# Trans_Main_Board_ESP32_NEW_Rev1_2.net
KiCad netlist of a schematic drawn in EAGLE
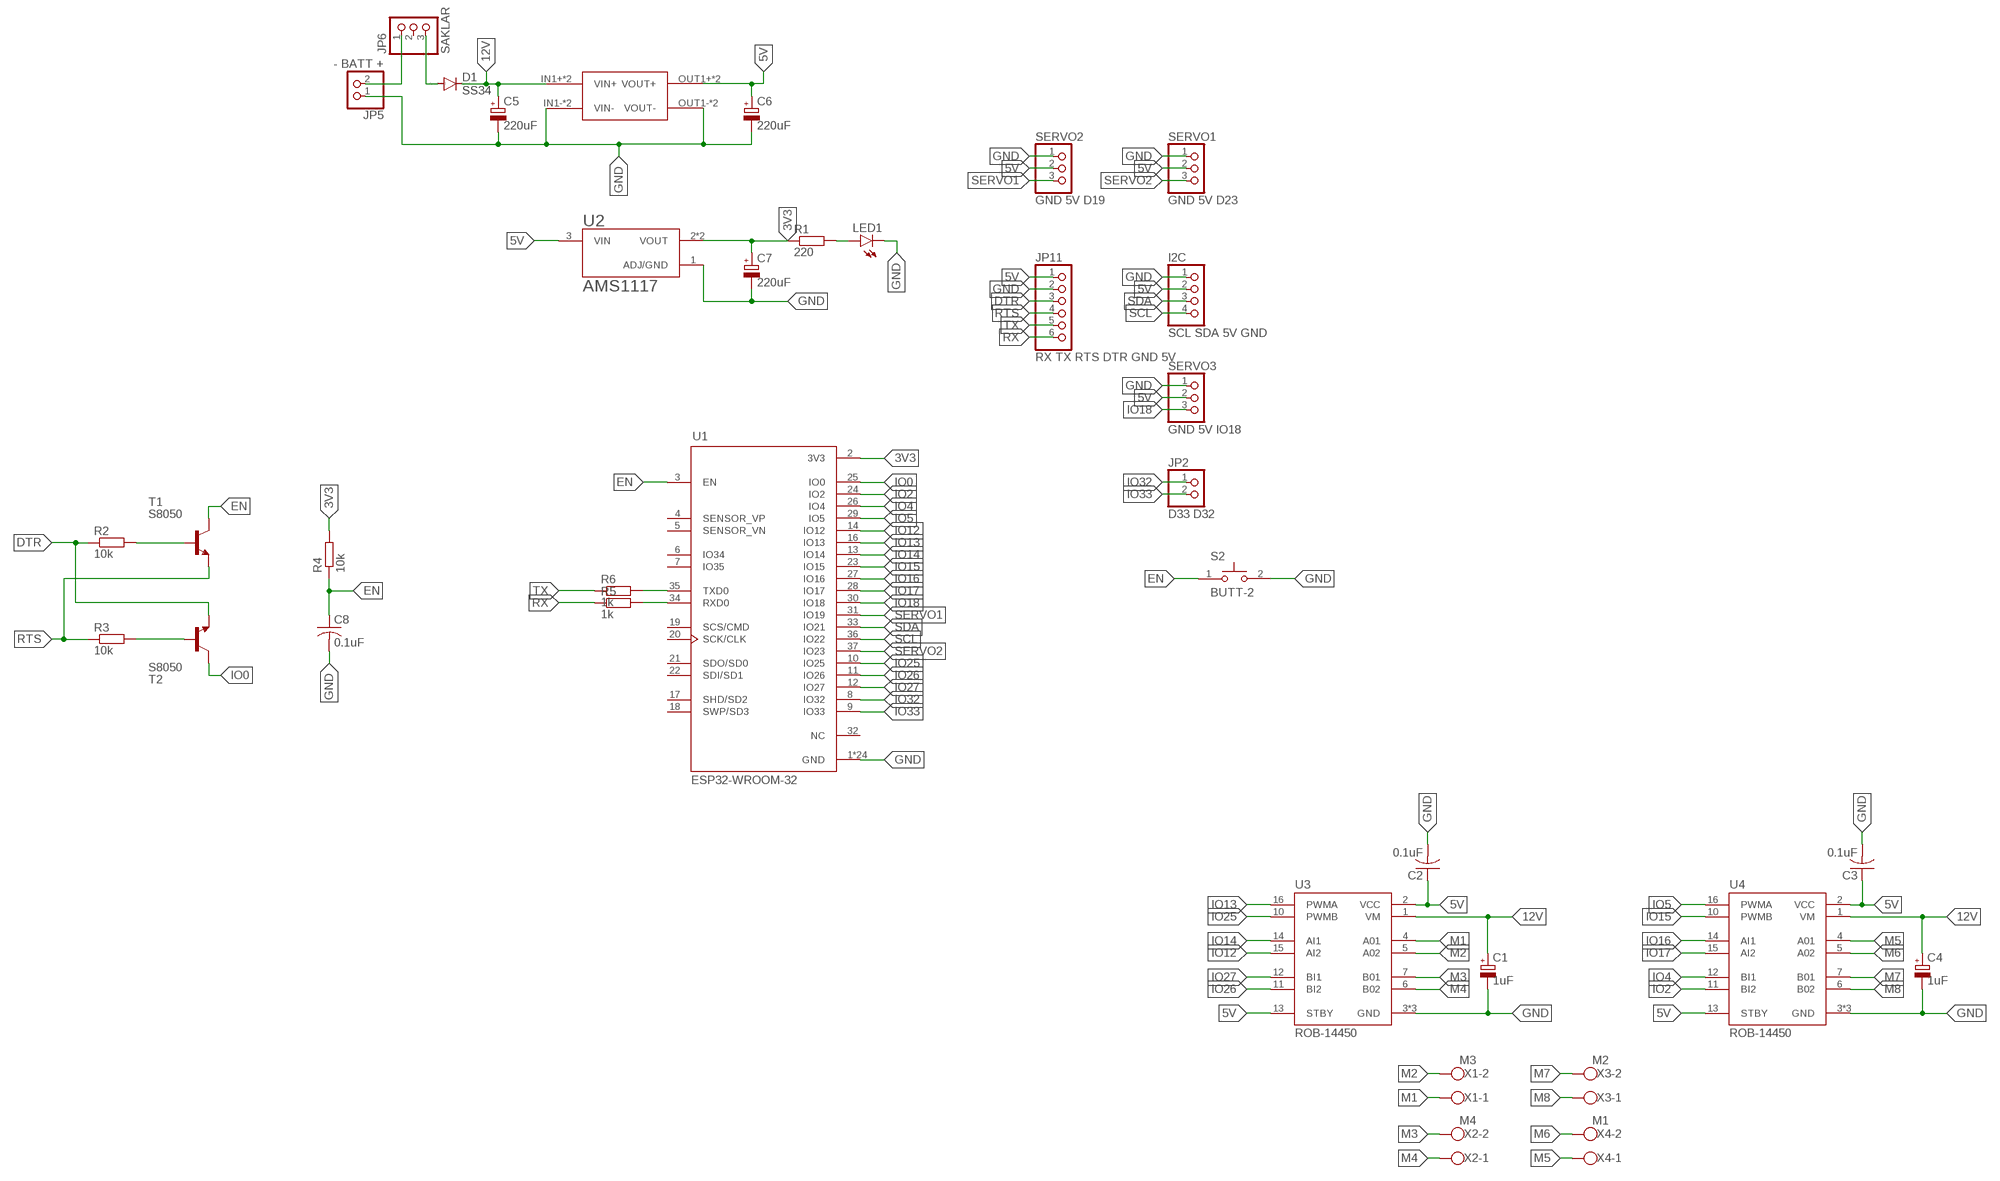
[diagram p0: schematic, sheet 1]

(export (version "E")
  (design (tool "Eeschema 10.0.6"))
  (components
    (comp (ref "C1")
      (value "1uF")
      (footprint "eagle-import:E2-5")
      (libsource (lib "eagle-import") (part "CPOL-EUE2-5"))
    )
    (comp (ref "C2")
      (value "0.1uF")
      (footprint "eagle-import:C1206")
      (libsource (lib "eagle-import") (part "C-USC1206"))
    )
    (comp (ref "C3")
      (value "0.1uF")
      (footprint "eagle-import:C1206")
      (libsource (lib "eagle-import") (part "C-USC1206"))
    )
    (comp (ref "C4")
      (value "1uF")
      (footprint "eagle-import:E2-5")
      (libsource (lib "eagle-import") (part "CPOL-EUE2-5"))
    )
    (comp (ref "C5")
      (value "220uF")
      (footprint "eagle-import:E2-5")
      (libsource (lib "eagle-import") (part "CPOL-EUE2-5"))
    )
    (comp (ref "C6")
      (value "220uF")
      (footprint "eagle-import:E2-5")
      (libsource (lib "eagle-import") (part "CPOL-EUE2-5"))
    )
    (comp (ref "C7")
      (value "220uF")
      (footprint "eagle-import:E2-5")
      (libsource (lib "eagle-import") (part "CPOL-EUE2-5"))
    )
    (comp (ref "C8")
      (value "0.1uF")
      (footprint "eagle-import:C1206")
      (libsource (lib "eagle-import") (part "C-USC1206"))
    )
    (comp (ref "D1")
      (value "SS34")
      (footprint "eagle-import:DO-214AC")
      (libsource (lib "eagle-import") (part "DIODE-DO-214AC"))
    )
    (comp (ref "I2C")
      (value "SCL SDA 5V GND")
      (footprint "eagle-import:1X04")
      (libsource (lib "eagle-import") (part "PINHD-1X4"))
    )
    (comp (ref "JP2")
      (value "D33 D32")
      (footprint "eagle-import:1X02")
      (libsource (lib "eagle-import") (part "PINHD-1X2"))
    )
    (comp (ref "JP5")
      (value "- BATT +")
      (footprint "eagle-import:1X02")
      (libsource (lib "eagle-import") (part "PINHD-1X2"))
    )
    (comp (ref "JP6")
      (value "SAKLAR")
      (footprint "eagle-import:1X03")
      (libsource (lib "eagle-import") (part "PINHD-1X3"))
    )
    (comp (ref "JP11")
      (value "RX TX RTS DTR GND 5V")
      (footprint "eagle-import:1X06")
      (libsource (lib "eagle-import") (part "PINHD-1X6"))
    )
    (comp (ref "LED1")
      (value "LEDCHIPLED_1206")
      (footprint "eagle-import:CHIPLED_1206")
      (libsource (lib "eagle-import") (part "LEDCHIPLED_1206"))
    )
    (comp (ref "R1")
      (value "220")
      (footprint "eagle-import:R1206")
      (libsource (lib "eagle-import") (part "R-EU_R1206"))
    )
    (comp (ref "R2")
      (value "10k")
      (footprint "eagle-import:R1206")
      (libsource (lib "eagle-import") (part "R-EU_R1206"))
    )
    (comp (ref "R3")
      (value "10k")
      (footprint "eagle-import:R1206")
      (libsource (lib "eagle-import") (part "R-EU_R1206"))
    )
    (comp (ref "R4")
      (value "10k")
      (footprint "eagle-import:R1206")
      (libsource (lib "eagle-import") (part "R-EU_R1206"))
    )
    (comp (ref "R5")
      (value "1k")
      (footprint "eagle-import:R1206")
      (libsource (lib "eagle-import") (part "R-EU_R1206"))
    )
    (comp (ref "R6")
      (value "1k")
      (footprint "eagle-import:R1206")
      (libsource (lib "eagle-import") (part "R-EU_R1206"))
    )
    (comp (ref "S2")
      (value "BUTT-2")
      (footprint "eagle-import:SW_BUTT-2")
      (fields (field (name "MF") "Gravitech"))
      (libsource (lib "eagle-import") (part "BUTT-2"))
    )
    (comp (ref "SERVO1")
      (value "GND 5V D23")
      (footprint "eagle-import:1X03")
      (libsource (lib "eagle-import") (part "PINHD-1X3"))
    )
    (comp (ref "SERVO2")
      (value "GND 5V D19")
      (footprint "eagle-import:1X03")
      (libsource (lib "eagle-import") (part "PINHD-1X3"))
    )
    (comp (ref "SERVO3")
      (value "GND 5V IO18")
      (footprint "eagle-import:1X03")
      (libsource (lib "eagle-import") (part "PINHD-1X3"))
    )
    (comp (ref "T1")
      (value "S8050")
      (footprint "eagle-import:SOT23")
      (libsource (lib "eagle-import") (part "BC846"))
    )
    (comp (ref "T2")
      (value "S8050")
      (footprint "eagle-import:SOT23")
      (libsource (lib "eagle-import") (part "BC846"))
    )
    (comp (ref "U$1")
      (value "MP1584")
      (footprint "eagle-import:DC-BRICK")
      (libsource (lib "eagle-import") (part "MP1584"))
    )
    (comp (ref "U1")
      (value "ESP32-WROOM-32")
      (footprint "eagle-import:MODULE_ESP32-WROOM-32")
      (fields (field (name "MF") "Espressif Systems"))
      (libsource (lib "eagle-import") (part "ESP32-WROOM-32"))
    )
    (comp (ref "U2")
      (value "AMS1117")
      (footprint "eagle-import:SOT229P700X180-4N")
      (fields (field (name "MF") "Advanced Monolithic Systems"))
      (libsource (lib "eagle-import") (part "AMS1117"))
    )
    (comp (ref "U3")
      (value "ROB-14450")
      (footprint "eagle-import:MODULE_ROB-14450")
      (fields (field (name "MF") "SparkFun Electronics"))
      (libsource (lib "eagle-import") (part "ROB-14450"))
    )
    (comp (ref "U4")
      (value "ROB-14450")
      (footprint "eagle-import:MODULE_ROB-14450")
      (fields (field (name "MF") "SparkFun Electronics"))
      (libsource (lib "eagle-import") (part "ROB-14450"))
    )
    (comp (ref "X1")
      (value "M3")
      (footprint "eagle-import:W237-102")
      (fields (field (name "MPN") "237-102"))
      (libsource (lib "eagle-import") (part "W237-102"))
    )
    (comp (ref "X2")
      (value "M4")
      (footprint "eagle-import:W237-102")
      (fields (field (name "MPN") "237-102"))
      (libsource (lib "eagle-import") (part "W237-102"))
    )
    (comp (ref "X3")
      (value "M2")
      (footprint "eagle-import:W237-102")
      (fields (field (name "MPN") "237-102"))
      (libsource (lib "eagle-import") (part "W237-102"))
    )
    (comp (ref "X4")
      (value "M1")
      (footprint "eagle-import:W237-102")
      (fields (field (name "MPN") "237-102"))
      (libsource (lib "eagle-import") (part "W237-102"))
    )
  )
  (nets
    (net (code "1") (name "3V3") (class "Default")
      (node (ref "C7") (pin "+") (pinfunction "+_+") (pintype "passive"))
      (node (ref "R1") (pin "1") (pinfunction "1_1") (pintype "passive"))
      (node (ref "R4") (pin "2") (pinfunction "2_2") (pintype "passive"))
      (node (ref "U1") (pin "2") (pinfunction "3V3_2") (pintype "power_in"))
      (node (ref "U2") (pin "2") (pinfunction "VOUT_2") (pintype "output"))
      (node (ref "U2") (pin "4") (pinfunction "VOUT_4") (pintype "output"))
    )
    (net (code "2") (name "5V") (class "Default")
      (node (ref "C2") (pin "1") (pinfunction "1_1") (pintype "passive"))
      (node (ref "C3") (pin "1") (pinfunction "1_1") (pintype "passive"))
      (node (ref "C6") (pin "+") (pinfunction "+_+") (pintype "passive"))
      (node (ref "I2C") (pin "2") (pinfunction "2_2") (pintype "passive"))
      (node (ref "JP11") (pin "1") (pinfunction "1_1") (pintype "passive"))
      (node (ref "SERVO1") (pin "2") (pinfunction "2_2") (pintype "passive"))
      (node (ref "SERVO2") (pin "2") (pinfunction "2_2") (pintype "passive"))
      (node (ref "SERVO3") (pin "2") (pinfunction "2_2") (pintype "passive"))
      (node (ref "U$1") (pin "OUT1+") (pinfunction "VOUT+_OUT1+") (pintype "output"))
      (node (ref "U$1") (pin "OUT2+") (pinfunction "VOUT+_OUT2+") (pintype "output"))
      (node (ref "U2") (pin "3") (pinfunction "VIN_3") (pintype "input"))
      (node (ref "U3") (pin "13") (pinfunction "STBY_13") (pintype "input"))
      (node (ref "U3") (pin "2") (pinfunction "VCC_2") (pintype "power_in"))
      (node (ref "U4") (pin "13") (pinfunction "STBY_13") (pintype "input"))
      (node (ref "U4") (pin "2") (pinfunction "VCC_2") (pintype "power_in"))
    )
    (net (code "3") (name "12V") (class "Default")
      (node (ref "C1") (pin "+") (pinfunction "+_+") (pintype "passive"))
      (node (ref "C4") (pin "+") (pinfunction "+_+") (pintype "passive"))
      (node (ref "C5") (pin "+") (pinfunction "+_+") (pintype "passive"))
      (node (ref "D1") (pin "C") (pinfunction "C_C") (pintype "passive"))
      (node (ref "U$1") (pin "IN1+") (pinfunction "VIN+_IN1+") (pintype "input"))
      (node (ref "U$1") (pin "IN2+") (pinfunction "VIN+_IN2+") (pintype "input"))
      (node (ref "U3") (pin "1") (pinfunction "VM_1") (pintype "power_in"))
      (node (ref "U4") (pin "1") (pinfunction "VM_1") (pintype "power_in"))
    )
    (net (code "4") (name "DTR") (class "Default")
      (node (ref "JP11") (pin "3") (pinfunction "3_3") (pintype "passive"))
      (node (ref "R2") (pin "1") (pinfunction "1_1") (pintype "passive"))
      (node (ref "T2") (pin "2") (pinfunction "E_2") (pintype "passive"))
    )
    (net (code "5") (name "EN") (class "Default")
      (node (ref "C8") (pin "1") (pinfunction "1_1") (pintype "passive"))
      (node (ref "R4") (pin "1") (pinfunction "1_1") (pintype "passive"))
      (node (ref "S2") (pin "1") (pinfunction "1_1") (pintype "passive"))
      (node (ref "T1") (pin "3") (pinfunction "C_3") (pintype "passive"))
      (node (ref "U1") (pin "3") (pinfunction "EN_3") (pintype "input"))
    )
    (net (code "6") (name "GND") (class "Default")
      (node (ref "C1") (pin "-") (pinfunction "-_-") (pintype "passive"))
      (node (ref "C2") (pin "2") (pinfunction "2_2") (pintype "passive"))
      (node (ref "C3") (pin "2") (pinfunction "2_2") (pintype "passive"))
      (node (ref "C4") (pin "-") (pinfunction "-_-") (pintype "passive"))
      (node (ref "C5") (pin "-") (pinfunction "-_-") (pintype "passive"))
      (node (ref "C6") (pin "-") (pinfunction "-_-") (pintype "passive"))
      (node (ref "C7") (pin "-") (pinfunction "-_-") (pintype "passive"))
      (node (ref "C8") (pin "2") (pinfunction "2_2") (pintype "passive"))
      (node (ref "I2C") (pin "1") (pinfunction "1_1") (pintype "passive"))
      (node (ref "JP11") (pin "2") (pinfunction "2_2") (pintype "passive"))
      (node (ref "JP5") (pin "1") (pinfunction "1_1") (pintype "passive"))
      (node (ref "LED1") (pin "C") (pinfunction "C_C") (pintype "passive"))
      (node (ref "S2") (pin "2") (pinfunction "2_2") (pintype "passive"))
      (node (ref "SERVO1") (pin "1") (pinfunction "1_1") (pintype "passive"))
      (node (ref "SERVO2") (pin "1") (pinfunction "1_1") (pintype "passive"))
      (node (ref "SERVO3") (pin "1") (pinfunction "1_1") (pintype "passive"))
      (node (ref "U$1") (pin "IN1-") (pinfunction "VIN-_IN1-") (pintype "input"))
      (node (ref "U$1") (pin "IN2-") (pinfunction "VIN-_IN2-") (pintype "input"))
      (node (ref "U$1") (pin "OUT1-") (pinfunction "VOUT-_OUT1-") (pintype "output"))
      (node (ref "U$1") (pin "OUT2-") (pinfunction "VOUT-_OUT2-") (pintype "output"))
      (node (ref "U1") (pin "1") (pinfunction "GND_1") (pintype "power_in"))
      (node (ref "U1") (pin "15") (pinfunction "GND_15") (pintype "power_in"))
      (node (ref "U1") (pin "38") (pinfunction "GND_38") (pintype "power_in"))
      (node (ref "U1") (pin "39_1") (pinfunction "GND_39_1") (pintype "power_in"))
      (node (ref "U1") (pin "39_10") (pinfunction "GND_39_10") (pintype "power_in"))
      (node (ref "U1") (pin "39_11") (pinfunction "GND_39_11") (pintype "power_in"))
      (node (ref "U1") (pin "39_12") (pinfunction "GND_39_12") (pintype "power_in"))
      (node (ref "U1") (pin "39_13") (pinfunction "GND_39_13") (pintype "power_in"))
      (node (ref "U1") (pin "39_14") (pinfunction "GND_39_14") (pintype "power_in"))
      (node (ref "U1") (pin "39_15") (pinfunction "GND_39_15") (pintype "power_in"))
      (node (ref "U1") (pin "39_16") (pinfunction "GND_39_16") (pintype "power_in"))
      (node (ref "U1") (pin "39_17") (pinfunction "GND_39_17") (pintype "power_in"))
      (node (ref "U1") (pin "39_18") (pinfunction "GND_39_18") (pintype "power_in"))
      (node (ref "U1") (pin "39_19") (pinfunction "GND_39_19") (pintype "power_in"))
      (node (ref "U1") (pin "39_2") (pinfunction "GND_39_2") (pintype "power_in"))
      (node (ref "U1") (pin "39_20") (pinfunction "GND_39_20") (pintype "power_in"))
      (node (ref "U1") (pin "39_21") (pinfunction "GND_39_21") (pintype "power_in"))
      (node (ref "U1") (pin "39_3") (pinfunction "GND_39_3") (pintype "power_in"))
      (node (ref "U1") (pin "39_4") (pinfunction "GND_39_4") (pintype "power_in"))
      (node (ref "U1") (pin "39_5") (pinfunction "GND_39_5") (pintype "power_in"))
      (node (ref "U1") (pin "39_6") (pinfunction "GND_39_6") (pintype "power_in"))
      (node (ref "U1") (pin "39_7") (pinfunction "GND_39_7") (pintype "power_in"))
      (node (ref "U1") (pin "39_8") (pinfunction "GND_39_8") (pintype "power_in"))
      (node (ref "U1") (pin "39_9") (pinfunction "GND_39_9") (pintype "power_in"))
      (node (ref "U2") (pin "1") (pinfunction "ADJ/GND_1") (pintype "power_in"))
      (node (ref "U3") (pin "3") (pinfunction "GND_3") (pintype "power_in"))
      (node (ref "U3") (pin "8") (pinfunction "GND_8") (pintype "power_in"))
      (node (ref "U3") (pin "9") (pinfunction "GND_9") (pintype "power_in"))
      (node (ref "U4") (pin "3") (pinfunction "GND_3") (pintype "power_in"))
      (node (ref "U4") (pin "8") (pinfunction "GND_8") (pintype "power_in"))
      (node (ref "U4") (pin "9") (pinfunction "GND_9") (pintype "power_in"))
    )
    (net (code "7") (name "IO0") (class "Default")
      (node (ref "T2") (pin "3") (pinfunction "C_3") (pintype "passive"))
      (node (ref "U1") (pin "25") (pinfunction "IO0_25") (pintype "bidirectional"))
    )
    (net (code "8") (name "IO2") (class "Default")
      (node (ref "U1") (pin "24") (pinfunction "IO2_24") (pintype "bidirectional"))
      (node (ref "U4") (pin "11") (pinfunction "BI2_11") (pintype "input"))
    )
    (net (code "9") (name "IO4") (class "Default")
      (node (ref "U1") (pin "26") (pinfunction "IO4_26") (pintype "bidirectional"))
      (node (ref "U4") (pin "12") (pinfunction "BI1_12") (pintype "input"))
    )
    (net (code "10") (name "IO5") (class "Default")
      (node (ref "U1") (pin "29") (pinfunction "IO5_29") (pintype "bidirectional"))
      (node (ref "U4") (pin "16") (pinfunction "PWMA_16") (pintype "input"))
    )
    (net (code "11") (name "IO12") (class "Default")
      (node (ref "U1") (pin "14") (pinfunction "IO12_14") (pintype "bidirectional"))
      (node (ref "U3") (pin "15") (pinfunction "AI2_15") (pintype "input"))
    )
    (net (code "12") (name "IO13") (class "Default")
      (node (ref "U1") (pin "16") (pinfunction "IO13_16") (pintype "bidirectional"))
      (node (ref "U3") (pin "16") (pinfunction "PWMA_16") (pintype "input"))
    )
    (net (code "13") (name "IO14") (class "Default")
      (node (ref "U1") (pin "13") (pinfunction "IO14_13") (pintype "bidirectional"))
      (node (ref "U3") (pin "14") (pinfunction "AI1_14") (pintype "input"))
    )
    (net (code "14") (name "IO15") (class "Default")
      (node (ref "U1") (pin "23") (pinfunction "IO15_23") (pintype "bidirectional"))
      (node (ref "U4") (pin "10") (pinfunction "PWMB_10") (pintype "input"))
    )
    (net (code "15") (name "IO16") (class "Default")
      (node (ref "U1") (pin "27") (pinfunction "IO16_27") (pintype "bidirectional"))
      (node (ref "U4") (pin "14") (pinfunction "AI1_14") (pintype "input"))
    )
    (net (code "16") (name "IO17") (class "Default")
      (node (ref "U1") (pin "28") (pinfunction "IO17_28") (pintype "bidirectional"))
      (node (ref "U4") (pin "15") (pinfunction "AI2_15") (pintype "input"))
    )
    (net (code "17") (name "IO18") (class "Default")
      (node (ref "SERVO3") (pin "3") (pinfunction "3_3") (pintype "passive"))
      (node (ref "U1") (pin "30") (pinfunction "IO18_30") (pintype "bidirectional"))
    )
    (net (code "18") (name "IO25") (class "Default")
      (node (ref "U1") (pin "10") (pinfunction "IO25_10") (pintype "bidirectional"))
      (node (ref "U3") (pin "10") (pinfunction "PWMB_10") (pintype "input"))
    )
    (net (code "19") (name "IO26") (class "Default")
      (node (ref "U1") (pin "11") (pinfunction "IO26_11") (pintype "bidirectional"))
      (node (ref "U3") (pin "11") (pinfunction "BI2_11") (pintype "input"))
    )
    (net (code "20") (name "IO27") (class "Default")
      (node (ref "U1") (pin "12") (pinfunction "IO27_12") (pintype "bidirectional"))
      (node (ref "U3") (pin "12") (pinfunction "BI1_12") (pintype "input"))
    )
    (net (code "21") (name "IO32") (class "Default")
      (node (ref "JP2") (pin "1") (pinfunction "1_1") (pintype "passive"))
      (node (ref "U1") (pin "8") (pinfunction "IO32_8") (pintype "bidirectional"))
    )
    (net (code "22") (name "IO33") (class "Default")
      (node (ref "JP2") (pin "2") (pinfunction "2_2") (pintype "passive"))
      (node (ref "U1") (pin "9") (pinfunction "IO33_9") (pintype "bidirectional"))
    )
    (net (code "23") (name "M1") (class "Default")
      (node (ref "U3") (pin "4") (pinfunction "A01_4") (pintype "output"))
      (node (ref "X1") (pin "1") (pinfunction "KL_1") (pintype "passive"))
    )
    (net (code "24") (name "M2") (class "Default")
      (node (ref "U3") (pin "5") (pinfunction "A02_5") (pintype "output"))
      (node (ref "X1") (pin "2") (pinfunction "KL_2") (pintype "passive"))
    )
    (net (code "25") (name "M3") (class "Default")
      (node (ref "U3") (pin "7") (pinfunction "B01_7") (pintype "output"))
      (node (ref "X2") (pin "2") (pinfunction "KL_2") (pintype "passive"))
    )
    (net (code "26") (name "M4") (class "Default")
      (node (ref "U3") (pin "6") (pinfunction "B02_6") (pintype "output"))
      (node (ref "X2") (pin "1") (pinfunction "KL_1") (pintype "passive"))
    )
    (net (code "27") (name "M5") (class "Default")
      (node (ref "U4") (pin "4") (pinfunction "A01_4") (pintype "output"))
      (node (ref "X4") (pin "1") (pinfunction "KL_1") (pintype "passive"))
    )
    (net (code "28") (name "M6") (class "Default")
      (node (ref "U4") (pin "5") (pinfunction "A02_5") (pintype "output"))
      (node (ref "X4") (pin "2") (pinfunction "KL_2") (pintype "passive"))
    )
    (net (code "29") (name "M7") (class "Default")
      (node (ref "U4") (pin "7") (pinfunction "B01_7") (pintype "output"))
      (node (ref "X3") (pin "2") (pinfunction "KL_2") (pintype "passive"))
    )
    (net (code "30") (name "M8") (class "Default")
      (node (ref "U4") (pin "6") (pinfunction "B02_6") (pintype "output"))
      (node (ref "X3") (pin "1") (pinfunction "KL_1") (pintype "passive"))
    )
    (net (code "31") (name "Net-(D1-PadA)") (class "Default")
      (node (ref "D1") (pin "A") (pinfunction "A_A") (pintype "passive"))
      (node (ref "JP6") (pin "3") (pinfunction "3_3") (pintype "passive"))
    )
    (net (code "32") (name "Net-(JP5-Pad2)") (class "Default")
      (node (ref "JP5") (pin "2") (pinfunction "2_2") (pintype "passive"))
      (node (ref "JP6") (pin "1") (pinfunction "1_1") (pintype "passive"))
    )
    (net (code "33") (name "Net-(LED1-PadA)") (class "Default")
      (node (ref "LED1") (pin "A") (pinfunction "A_A") (pintype "passive"))
      (node (ref "R1") (pin "2") (pinfunction "2_2") (pintype "passive"))
    )
    (net (code "34") (name "Net-(T1-B)") (class "Default")
      (node (ref "R2") (pin "2") (pinfunction "2_2") (pintype "passive"))
      (node (ref "T1") (pin "1") (pinfunction "B_1") (pintype "passive"))
    )
    (net (code "35") (name "Net-(T2-B)") (class "Default")
      (node (ref "R3") (pin "2") (pinfunction "2_2") (pintype "passive"))
      (node (ref "T2") (pin "1") (pinfunction "B_1") (pintype "passive"))
    )
    (net (code "36") (name "Net-(U1-RXD0)") (class "Default")
      (node (ref "R5") (pin "2") (pinfunction "2_2") (pintype "passive"))
      (node (ref "U1") (pin "34") (pinfunction "RXD0_34") (pintype "bidirectional"))
    )
    (net (code "37") (name "Net-(U1-TXD0)") (class "Default")
      (node (ref "R6") (pin "2") (pinfunction "2_2") (pintype "passive"))
      (node (ref "U1") (pin "35") (pinfunction "TXD0_35") (pintype "bidirectional"))
    )
    (net (code "38") (name "RTS") (class "Default")
      (node (ref "JP11") (pin "4") (pinfunction "4_4") (pintype "passive"))
      (node (ref "R3") (pin "1") (pinfunction "1_1") (pintype "passive"))
      (node (ref "T1") (pin "2") (pinfunction "E_2") (pintype "passive"))
    )
    (net (code "39") (name "RX") (class "Default")
      (node (ref "JP11") (pin "6") (pinfunction "6_6") (pintype "passive"))
      (node (ref "R5") (pin "1") (pinfunction "1_1") (pintype "passive"))
    )
    (net (code "40") (name "SCL") (class "Default")
      (node (ref "I2C") (pin "4") (pinfunction "4_4") (pintype "passive"))
      (node (ref "U1") (pin "36") (pinfunction "IO22_36") (pintype "bidirectional"))
    )
    (net (code "41") (name "SDA") (class "Default")
      (node (ref "I2C") (pin "3") (pinfunction "3_3") (pintype "passive"))
      (node (ref "U1") (pin "33") (pinfunction "IO21_33") (pintype "bidirectional"))
    )
    (net (code "42") (name "SERVO1") (class "Default")
      (node (ref "SERVO2") (pin "3") (pinfunction "3_3") (pintype "passive"))
      (node (ref "U1") (pin "31") (pinfunction "IO19_31") (pintype "bidirectional"))
    )
    (net (code "43") (name "SERVO2") (class "Default")
      (node (ref "SERVO1") (pin "3") (pinfunction "3_3") (pintype "passive"))
      (node (ref "U1") (pin "37") (pinfunction "IO23_37") (pintype "bidirectional"))
    )
    (net (code "44") (name "TX") (class "Default")
      (node (ref "JP11") (pin "5") (pinfunction "5_5") (pintype "passive"))
      (node (ref "R6") (pin "1") (pinfunction "1_1") (pintype "passive"))
    )
    (net (code "45") (name "unconnected-(JP6-Pad2)") (class "Default")
      (node (ref "JP6") (pin "2") (pinfunction "2_2") (pintype "passive"))
    )
    (net (code "46") (name "unconnected-(U1-IO34-Pad6)") (class "Default")
      (node (ref "U1") (pin "6") (pinfunction "IO34_6") (pintype "input"))
    )
    (net (code "47") (name "unconnected-(U1-IO35-Pad7)") (class "Default")
      (node (ref "U1") (pin "7") (pinfunction "IO35_7") (pintype "input"))
    )
    (net (code "48") (name "unconnected-(U1-NC-Pad32)") (class "Default")
      (node (ref "U1") (pin "32") (pinfunction "NC_32") (pintype "no_connect"))
    )
    (net (code "49") (name "unconnected-(U1-SCK{slash}CLK-Pad20)") (class "Default")
      (node (ref "U1") (pin "20") (pinfunction "SCK/CLK_20") (pintype "bidirectional"))
    )
    (net (code "50") (name "unconnected-(U1-SCS{slash}CMD-Pad19)") (class "Default")
      (node (ref "U1") (pin "19") (pinfunction "SCS/CMD_19") (pintype "bidirectional"))
    )
    (net (code "51") (name "unconnected-(U1-SDI{slash}SD1-Pad22)") (class "Default")
      (node (ref "U1") (pin "22") (pinfunction "SDI/SD1_22") (pintype "bidirectional"))
    )
    (net (code "52") (name "unconnected-(U1-SDO{slash}SD0-Pad21)") (class "Default")
      (node (ref "U1") (pin "21") (pinfunction "SDO/SD0_21") (pintype "bidirectional"))
    )
    (net (code "53") (name "unconnected-(U1-SENSOR_VN-Pad5)") (class "Default")
      (node (ref "U1") (pin "5") (pinfunction "SENSOR_VN_5") (pintype "input"))
    )
    (net (code "54") (name "unconnected-(U1-SENSOR_VP-Pad4)") (class "Default")
      (node (ref "U1") (pin "4") (pinfunction "SENSOR_VP_4") (pintype "input"))
    )
    (net (code "55") (name "unconnected-(U1-SHD{slash}SD2-Pad17)") (class "Default")
      (node (ref "U1") (pin "17") (pinfunction "SHD/SD2_17") (pintype "bidirectional"))
    )
    (net (code "56") (name "unconnected-(U1-SWP{slash}SD3-Pad18)") (class "Default")
      (node (ref "U1") (pin "18") (pinfunction "SWP/SD3_18") (pintype "bidirectional"))
    )
  )
)
